# STM32.net
KiCad netlist of a schematic drawn in Altium Designer
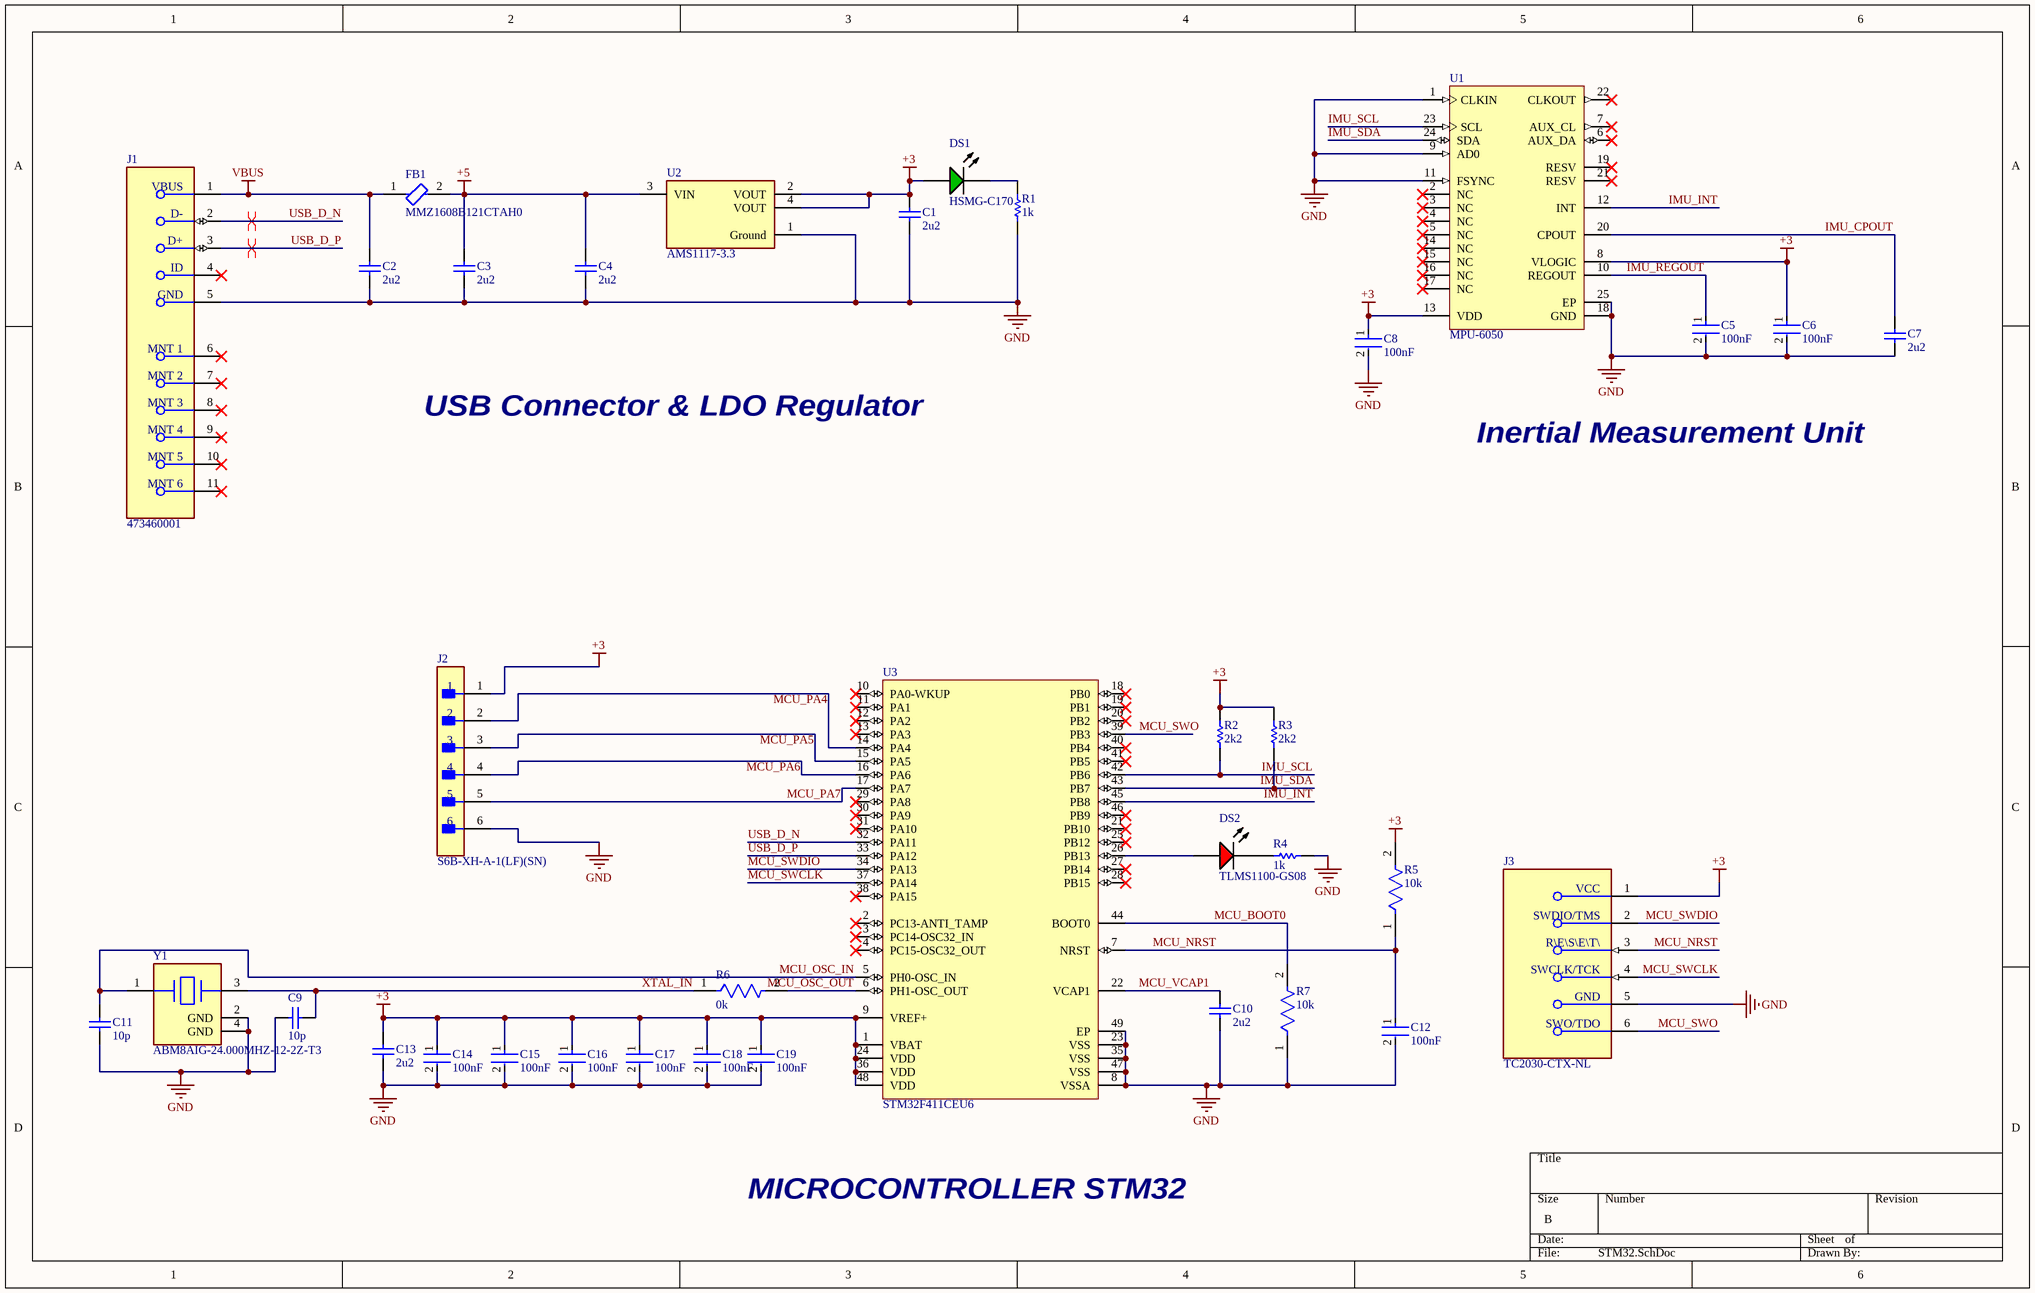
[diagram p0: STM32.SchDoc]

(export (version "E")
  (design (tool "Eeschema 10.0.6"))
  (components
    (comp (ref "C1")
      (value "2u2")
      (footprint "CAPC2013X135X50ML10T20")
      (fields (field (name "MANUFACTURER") "Murata") (field (name "PART NUMBER") "GRM21BR71C225KA12L"))
      (libsource (lib "Altium Content Vault") (part "CAP"))
    )
    (comp (ref "C2")
      (value "2u2")
      (footprint "CAPC2013X135X50ML10T20")
      (fields (field (name "MANUFACTURER") "Murata") (field (name "PART NUMBER") "GRM21BR71C225KA12L"))
      (libsource (lib "Altium Content Vault") (part "CAP"))
    )
    (comp (ref "C3")
      (value "2u2")
      (footprint "CAPC2013X135X50ML10T20")
      (fields (field (name "MANUFACTURER") "Murata") (field (name "PART NUMBER") "GRM21BR71C225KA12L"))
      (libsource (lib "Altium Content Vault") (part "CAP"))
    )
    (comp (ref "C4")
      (value "2u2")
      (footprint "CAPC2013X135X50ML10T20")
      (fields (field (name "MANUFACTURER") "Murata") (field (name "PART NUMBER") "GRM21BR71C225KA12L"))
      (libsource (lib "Altium Content Vault") (part "CAP"))
    )
    (comp (ref "C5")
      (value "100nF")
      (footprint "FP-C0603C-CF-MFG")
      (description "Capacitor; Ceramic; Cap; .100uF; Tol 10%; SMT; Vol-Rtg 16V; X7R; Tape and Reel")
      (fields
        (field (name "MANUFACTURER PART NUMBER") "C0603C104K4RACTU")
        (field (name "OCTOPART") "https://octopart.com/c0603c104k4ractu-kemet-93067")
      )
      (libsource (lib "Altium Content Vault") (part "b4654b650e69147ec39a6b967a45e02"))
    )
    (comp (ref "C6")
      (value "100nF")
      (footprint "FP-C0603C-CF-MFG")
      (description "Capacitor; Ceramic; Cap; .100uF; Tol 10%; SMT; Vol-Rtg 16V; X7R; Tape and Reel")
      (fields
        (field (name "MANUFACTURER PART NUMBER") "C0603C104K4RACTU")
        (field (name "OCTOPART") "https://octopart.com/c0603c104k4ractu-kemet-93067")
      )
      (libsource (lib "Altium Content Vault") (part "b4654b650e69147ec39a6b967a45e02"))
    )
    (comp (ref "C7")
      (value "2u2")
      (footprint "CAPC2013X135X50ML10T20")
      (fields (field (name "MANUFACTURER") "Murata") (field (name "PART NUMBER") "GRM21BR71C225KA12L"))
      (libsource (lib "Altium Content Vault") (part "CAP"))
    )
    (comp (ref "C8")
      (value "100nF")
      (footprint "FP-C0603C-CF-MFG")
      (description "Capacitor; Ceramic; Cap; .100uF; Tol 10%; SMT; Vol-Rtg 16V; X7R; Tape and Reel")
      (fields
        (field (name "MANUFACTURER PART NUMBER") "C0603C104K4RACTU")
        (field (name "OCTOPART") "https://octopart.com/c0603c104k4ractu-kemet-93067")
      )
      (libsource (lib "Altium Content Vault") (part "b4654b650e69147ec39a6b967a45e02"))
    )
    (comp (ref "C9")
      (value "10p")
      (footprint "CAPC1006X50X20ML10T10")
      (fields
        (field (name "MANUFACTURER") "AVX Interconnect / Elco")
        (field (name "PART NUMBER") "0402YJ100FBSTR")
      )
      (libsource (lib "Altium Content Vault") (part "CAP"))
    )
    (comp (ref "C10")
      (value "2u2")
      (footprint "CAPC2013X135X50ML10T20")
      (fields (field (name "MANUFACTURER") "Murata") (field (name "PART NUMBER") "GRM21BR71C225KA12L"))
      (libsource (lib "Altium Content Vault") (part "CAP"))
    )
    (comp (ref "C11")
      (value "10p")
      (footprint "CAPC1006X50X20ML10T10")
      (fields
        (field (name "MANUFACTURER") "AVX Interconnect / Elco")
        (field (name "PART NUMBER") "0402YJ100FBSTR")
      )
      (libsource (lib "Altium Content Vault") (part "CAP"))
    )
    (comp (ref "C12")
      (value "100nF")
      (footprint "FP-C0603C-CF-MFG")
      (description "Capacitor; Ceramic; Cap; .100uF; Tol 10%; SMT; Vol-Rtg 16V; X7R; Tape and Reel")
      (fields
        (field (name "MANUFACTURER PART NUMBER") "C0603C104K4RACTU")
        (field (name "OCTOPART") "https://octopart.com/c0603c104k4ractu-kemet-93067")
      )
      (libsource (lib "Altium Content Vault") (part "b4654b650e69147ec39a6b967a45e02"))
    )
    (comp (ref "C13")
      (value "2u2")
      (footprint "CAPC2013X135X50ML10T20")
      (fields (field (name "MANUFACTURER") "Murata") (field (name "PART NUMBER") "GRM21BR71C225KA12L"))
      (libsource (lib "Altium Content Vault") (part "CAP"))
    )
    (comp (ref "C14")
      (value "100nF")
      (footprint "FP-C0603C-CF-MFG")
      (description "Capacitor; Ceramic; Cap; .100uF; Tol 10%; SMT; Vol-Rtg 16V; X7R; Tape and Reel")
      (fields
        (field (name "MANUFACTURER PART NUMBER") "C0603C104K4RACTU")
        (field (name "OCTOPART") "https://octopart.com/c0603c104k4ractu-kemet-93067")
      )
      (libsource (lib "Altium Content Vault") (part "b4654b650e69147ec39a6b967a45e02"))
    )
    (comp (ref "C15")
      (value "100nF")
      (footprint "FP-C0603C-CF-MFG")
      (description "Capacitor; Ceramic; Cap; .100uF; Tol 10%; SMT; Vol-Rtg 16V; X7R; Tape and Reel")
      (fields
        (field (name "MANUFACTURER PART NUMBER") "C0603C104K4RACTU")
        (field (name "OCTOPART") "https://octopart.com/c0603c104k4ractu-kemet-93067")
      )
      (libsource (lib "Altium Content Vault") (part "b4654b650e69147ec39a6b967a45e02"))
    )
    (comp (ref "C16")
      (value "100nF")
      (footprint "FP-C0603C-CF-MFG")
      (description "Capacitor; Ceramic; Cap; .100uF; Tol 10%; SMT; Vol-Rtg 16V; X7R; Tape and Reel")
      (fields
        (field (name "MANUFACTURER PART NUMBER") "C0603C104K4RACTU")
        (field (name "OCTOPART") "https://octopart.com/c0603c104k4ractu-kemet-93067")
      )
      (libsource (lib "Altium Content Vault") (part "b4654b650e69147ec39a6b967a45e02"))
    )
    (comp (ref "C17")
      (value "100nF")
      (footprint "FP-C0603C-CF-MFG")
      (description "Capacitor; Ceramic; Cap; .100uF; Tol 10%; SMT; Vol-Rtg 16V; X7R; Tape and Reel")
      (fields
        (field (name "MANUFACTURER PART NUMBER") "C0603C104K4RACTU")
        (field (name "OCTOPART") "https://octopart.com/c0603c104k4ractu-kemet-93067")
      )
      (libsource (lib "Altium Content Vault") (part "b4654b650e69147ec39a6b967a45e02"))
    )
    (comp (ref "C18")
      (value "100nF")
      (footprint "FP-C0603C-CF-MFG")
      (description "Capacitor; Ceramic; Cap; .100uF; Tol 10%; SMT; Vol-Rtg 16V; X7R; Tape and Reel")
      (fields
        (field (name "MANUFACTURER PART NUMBER") "C0603C104K4RACTU")
        (field (name "OCTOPART") "https://octopart.com/c0603c104k4ractu-kemet-93067")
      )
      (libsource (lib "Altium Content Vault") (part "b4654b650e69147ec39a6b967a45e02"))
    )
    (comp (ref "C19")
      (value "100nF")
      (footprint "FP-C0603C-CF-MFG")
      (description "Capacitor; Ceramic; Cap; .100uF; Tol 10%; SMT; Vol-Rtg 16V; X7R; Tape and Reel")
      (fields
        (field (name "MANUFACTURER PART NUMBER") "C0603C104K4RACTU")
        (field (name "OCTOPART") "https://octopart.com/c0603c104k4ractu-kemet-93067")
      )
      (libsource (lib "Altium Content Vault") (part "b4654b650e69147ec39a6b967a45e02"))
    )
    (comp (ref "DS1")
      (value "HSMG-C170")
      (footprint "AVAG-HSMX-C170_V")
      (description "Chip LED, Green, 2.2 V, -40 to 85 degC, 2-Pin SMD, Pb-Free, Tape and Reel")
      (fields (field (name "MANUFACTURER") "Avago"))
      (libsource (lib "Altium Content Vault") (part "LED_GREEN_A1K2-2"))
    )
    (comp (ref "DS2")
      (value "TLMS1100-GS08")
      (footprint "VISH-TLMX1100_V")
      (description "LED, RED, 2.1 V, -40 to 100 degC, 2-Pin SMD (0603), RoHS, Tape and Reel")
      (fields (field (name "TOLERANCE") "5%"))
      (libsource (lib "Altium Content Vault") (part "LED-RED-AK-2"))
    )
    (comp (ref "FB1")
      (value "MMZ1608B121CTAH0")
      (footprint "FP-MMZ1608-0_6-MFG")
      (description "FERRITE BEAD 120 OHM 0603 1LN")
      (fields (field (name "TOLERANCE") "25%"))
      (libsource (lib "Altium Content Vault") (part "5f30dd21d616792df468990f7003faa"))
    )
    (comp (ref "J1")
      (value "473460001")
      (footprint "FP-473460001-MFG")
      (description "CONN RCPT USB2.0 MICRO B SMD R/A")
      (fields
        (field (name "OCTOPART") "https://octopart.com/47346-0001-molex-7164928")
        (field (name "MANUFACTURER") "Molex")
      )
      (libsource (lib "Altium Content Vault") (part "53ae1f1d9b557310b43ca686e5bb76a"))
    )
    (comp (ref "J2")
      (value "S6B-XH-A-1(LF)(SN)")
      (footprint "FP-S6B-XH-A-1_LF_SN-MFG")
      (description "CONN HEADER R/A P6OS 2.5MM")
      (libsource (lib "Altium Content Vault") (part "f2cb566baf1c37ab5a3b8e90bbeafd6"))
    )
    (comp (ref "J3")
      (value "TC2030-CTX-NL")
      (footprint "FP-TC2030-CTX-NL-MFG")
      (description "6-Pin “No legs” TC2030 Plug-of-Nails™ Cable for use with ARM Cortex processors")
      (libsource (lib "Altium Content Vault") (part "e3fe093a55dc37473f431e03719485e"))
    )
    (comp (ref "R1")
      (value "1k")
      (footprint "RESC2013X60X35ML10T20")
      (description "Chip Resistor, 1 KOhm, +/- 1%, 125 mW, -55 to 155 degC, 0805 (2012 Metric), RoHS, Tape and Reel")
      (fields (field (name "TOLERANCE") "1%") (field (name "MANUFACTURER") "Yageo"))
      (libsource (lib "Altium Content Vault") (part "RES-2"))
    )
    (comp (ref "R2")
      (value "2k2")
      (footprint "RESC1609X50X30ML10T20")
      (fields (field (name "MANUFACTURER") "Vishay Dale") (field (name "PART NUMBER") "CRCW06032R20FKEA"))
      (libsource (lib "Altium Content Vault") (part "RES"))
    )
    (comp (ref "R3")
      (value "2k2")
      (footprint "RESC1609X50X30ML10T20")
      (fields (field (name "MANUFACTURER") "Vishay Dale") (field (name "PART NUMBER") "CRCW06032R20FKEA"))
      (libsource (lib "Altium Content Vault") (part "RES"))
    )
    (comp (ref "R4")
      (value "1k")
      (footprint "RESC2013X60X35ML10T20")
      (description "Chip Resistor, 1 KOhm, +/- 1%, 125 mW, -55 to 155 degC, 0805 (2012 Metric), RoHS, Tape and Reel")
      (fields (field (name "TOLERANCE") "1%") (field (name "MANUFACTURER") "Yageo"))
      (libsource (lib "Altium Content Vault") (part "RES-2"))
    )
    (comp (ref "R5")
      (value "10k")
      (footprint "FP-CRCW0402-e3-IPC_B")
      (description "RES SMD 10K OHM 1% 1/16W 0402")
      (fields (field (name "TOLERANCE") "1%"))
      (libsource (lib "Altium Content Vault") (part "1029c3af85768c4190bb7ad29bc67b5"))
    )
    (comp (ref "R6")
      (value "0k")
      (footprint "FP-CRCW0402-e3-IPC_C")
      (description "RES Thick Film, 0Ω, 0.063W, 0402")
      (fields (field (name "TOLERANCE") "5%"))
      (libsource (lib "Altium Content Vault") (part "1029c3af85768c4190bb7ad29bc67b5"))
    )
    (comp (ref "R7")
      (value "10k")
      (footprint "FP-CRCW0402-e3-IPC_B")
      (description "RES SMD 10K OHM 1% 1/16W 0402")
      (fields (field (name "TOLERANCE") "1%"))
      (libsource (lib "Altium Content Vault") (part "1029c3af85768c4190bb7ad29bc67b5"))
    )
    (comp (ref "U1")
      (value "MPU-6050")
      (footprint "IS-QFN-24_V")
      (fields (field (name "MANUFACTURER") "InvenSense"))
      (libsource (lib "Altium Content Vault") (part "IS-MPU-6050-QFN-24"))
    )
    (comp (ref "U2")
      (value "AMS1117-3.3")
      (footprint "FP-AMS1117-IPC_C")
      (description "LDO Voltage Regulators 1A, 3.3V")
      (fields
        (field (name "OCTOPART") "https://octopart.com/ams1117-3.3-advanced+monolithic+systems-25899300")
        (field (name "MANUFACTURER") "Advanced Monolithic Systems")
      )
      (libsource (lib "Altium Content Vault") (part "8bdbb5f8e77002000e30dd2845d0354"))
    )
    (comp (ref "U3")
      (value "STM32F411CEU6")
      (footprint "STM-UFQFPN48_L")
      (libsource (lib "Altium Content Vault") (part "MC-ARM-STM32F411-UFQFPN48"))
    )
    (comp (ref "Y1")
      (value "ABM8AIG-24.000MHZ-12-2Z-T3")
      (footprint "FP-ABM8AIG-MFG")
      (description "Crystal 24MHz ±20ppm (Tol) ±50ppm (Stability) 12pF FUND 50Ω Automotive 4-Pin Ultra Mini-CSMD T/R")
      (libsource (lib "Altium Content Vault") (part "5645ab55de99a04feaa93ac4102b7fe"))
    )
  )
  (nets
    (net (code "1") (name "+3") (class "Default")
      (node (ref "C1") (pin "2") (pinfunction "2_2") (pintype "passive"))
      (node (ref "C13") (pin "2") (pinfunction "2_2") (pintype "passive"))
      (node (ref "C14") (pin "1") (pinfunction "1_1") (pintype "passive"))
      (node (ref "C15") (pin "1") (pinfunction "1_1") (pintype "passive"))
      (node (ref "C16") (pin "1") (pinfunction "1_1") (pintype "passive"))
      (node (ref "C17") (pin "1") (pinfunction "1_1") (pintype "passive"))
      (node (ref "C18") (pin "1") (pinfunction "1_1") (pintype "passive"))
      (node (ref "C19") (pin "1") (pinfunction "1_1") (pintype "passive"))
      (node (ref "C6") (pin "1") (pinfunction "1_1") (pintype "passive"))
      (node (ref "C8") (pin "1") (pinfunction "1_1") (pintype "passive"))
      (node (ref "DS1") (pin "1") (pinfunction "A_1") (pintype "passive"))
      (node (ref "J2") (pin "1") (pinfunction "1_1") (pintype "passive"))
      (node (ref "J3") (pin "1") (pinfunction "VCC_1") (pintype "power_in"))
      (node (ref "R2") (pin "2") (pinfunction "2_2") (pintype "passive"))
      (node (ref "R3") (pin "2") (pinfunction "2_2") (pintype "passive"))
      (node (ref "R5") (pin "2") (pinfunction "2_2") (pintype "passive"))
      (node (ref "U1") (pin "13") (pinfunction "VDD_13") (pintype "power_in"))
      (node (ref "U1") (pin "8") (pinfunction "VLOGIC_8") (pintype "power_in"))
      (node (ref "U2") (pin "2") (pinfunction "VOUT_2") (pintype "passive"))
      (node (ref "U2") (pin "4") (pinfunction "VOUT_4") (pintype "passive"))
      (node (ref "U3") (pin "1") (pinfunction "VBAT_1") (pintype "power_in"))
      (node (ref "U3") (pin "24") (pinfunction "VDD_24") (pintype "power_in"))
      (node (ref "U3") (pin "36") (pinfunction "VDD_36") (pintype "power_in"))
      (node (ref "U3") (pin "48") (pinfunction "VDD_48") (pintype "power_in"))
      (node (ref "U3") (pin "9") (pinfunction "VREF+_9") (pintype "power_in"))
    )
    (net (code "2") (name "+5") (class "Default")
      (node (ref "C3") (pin "2") (pinfunction "2_2") (pintype "passive"))
      (node (ref "C4") (pin "2") (pinfunction "2_2") (pintype "passive"))
      (node (ref "FB1") (pin "2") (pinfunction "2_2") (pintype "passive"))
      (node (ref "U2") (pin "3") (pinfunction "VIN_3") (pintype "power_in"))
    )
    (net (code "3") (name "/IMU_CPOUT") (class "Default")
      (node (ref "C7") (pin "2") (pinfunction "2_2") (pintype "passive"))
      (node (ref "U1") (pin "20") (pinfunction "CPOUT_20") (pintype "passive"))
    )
    (net (code "4") (name "/IMU_INT") (class "Default")
      (node (ref "U1") (pin "12") (pinfunction "INT_12") (pintype "open_collector"))
      (node (ref "U3") (pin "45") (pinfunction "PB8_45") (pintype "bidirectional"))
    )
    (net (code "5") (name "/IMU_REGOUT") (class "Default")
      (node (ref "C5") (pin "1") (pinfunction "1_1") (pintype "passive"))
      (node (ref "U1") (pin "10") (pinfunction "REGOUT_10") (pintype "passive"))
    )
    (net (code "6") (name "/IMU_SCL") (class "Default")
      (node (ref "R2") (pin "1") (pinfunction "1_1") (pintype "passive"))
      (node (ref "U1") (pin "23") (pinfunction "SCL_23") (pintype "input"))
      (node (ref "U3") (pin "42") (pinfunction "PB6_42") (pintype "bidirectional"))
    )
    (net (code "7") (name "/IMU_SDA") (class "Default")
      (node (ref "R3") (pin "1") (pinfunction "1_1") (pintype "passive"))
      (node (ref "U1") (pin "24") (pinfunction "SDA_24") (pintype "bidirectional"))
      (node (ref "U3") (pin "43") (pinfunction "PB7_43") (pintype "bidirectional"))
    )
    (net (code "8") (name "/MCU_BOOT0") (class "Default")
      (node (ref "R7") (pin "2") (pinfunction "2_2") (pintype "passive"))
      (node (ref "U3") (pin "44") (pinfunction "BOOT0_44") (pintype "passive"))
    )
    (net (code "9") (name "/MCU_NRST") (class "Default")
      (node (ref "C12") (pin "1") (pinfunction "1_1") (pintype "passive"))
      (node (ref "J3") (pin "3") (pinfunction "~{RESET}_3") (pintype "input"))
      (node (ref "R5") (pin "1") (pinfunction "1_1") (pintype "passive"))
      (node (ref "U3") (pin "7") (pinfunction "NRST_7") (pintype "bidirectional"))
    )
    (net (code "10") (name "/MCU_OSC_IN") (class "Default")
      (node (ref "C11") (pin "2") (pinfunction "2_2") (pintype "passive"))
      (node (ref "U3") (pin "5") (pinfunction "PH0-OSC_IN_5") (pintype "bidirectional"))
      (node (ref "Y1") (pin "1") (pinfunction "1_1") (pintype "passive"))
    )
    (net (code "11") (name "/MCU_OSC_OUT") (class "Default")
      (node (ref "R6") (pin "2") (pinfunction "2_2") (pintype "passive"))
      (node (ref "U3") (pin "6") (pinfunction "PH1-OSC_OUT_6") (pintype "bidirectional"))
    )
    (net (code "12") (name "/MCU_PA4") (class "Default")
      (node (ref "J2") (pin "2") (pinfunction "2_2") (pintype "passive"))
      (node (ref "U3") (pin "14") (pinfunction "PA4_14") (pintype "bidirectional"))
    )
    (net (code "13") (name "/MCU_PA5") (class "Default")
      (node (ref "J2") (pin "3") (pinfunction "3_3") (pintype "passive"))
      (node (ref "U3") (pin "15") (pinfunction "PA5_15") (pintype "bidirectional"))
    )
    (net (code "14") (name "/MCU_PA6") (class "Default")
      (node (ref "J2") (pin "4") (pinfunction "4_4") (pintype "passive"))
      (node (ref "U3") (pin "16") (pinfunction "PA6_16") (pintype "bidirectional"))
    )
    (net (code "15") (name "/MCU_PA7") (class "Default")
      (node (ref "J2") (pin "5") (pinfunction "5_5") (pintype "passive"))
      (node (ref "U3") (pin "17") (pinfunction "PA7_17") (pintype "bidirectional"))
    )
    (net (code "16") (name "/MCU_SWCLK") (class "Default")
      (node (ref "J3") (pin "4") (pinfunction "SWCLK/TCK_4") (pintype "input"))
      (node (ref "U3") (pin "37") (pinfunction "PA14_37") (pintype "bidirectional"))
    )
    (net (code "17") (name "/MCU_SWDIO") (class "Default")
      (node (ref "J3") (pin "2") (pinfunction "SWDIO/TMS_2") (pintype "passive"))
      (node (ref "U3") (pin "34") (pinfunction "PA13_34") (pintype "bidirectional"))
    )
    (net (code "18") (name "/MCU_SWO") (class "Default")
      (node (ref "J3") (pin "6") (pinfunction "SWO/TDO_6") (pintype "passive"))
      (node (ref "U3") (pin "39") (pinfunction "PB3_39") (pintype "bidirectional"))
    )
    (net (code "19") (name "/MCU_VCAP1") (class "Default")
      (node (ref "C10") (pin "2") (pinfunction "2_2") (pintype "passive"))
      (node (ref "U3") (pin "22") (pinfunction "VCAP1_22") (pintype "passive"))
    )
    (net (code "20") (name "/USB_D_N") (class "Default")
      (node (ref "J1") (pin "2") (pinfunction "D-_2") (pintype "bidirectional"))
      (node (ref "U3") (pin "32") (pinfunction "PA11_32") (pintype "bidirectional"))
    )
    (net (code "21") (name "/USB_D_P") (class "Default")
      (node (ref "J1") (pin "3") (pinfunction "D+_3") (pintype "bidirectional"))
      (node (ref "U3") (pin "33") (pinfunction "PA12_33") (pintype "bidirectional"))
    )
    (net (code "22") (name "/XTAL_IN") (class "Default")
      (node (ref "C9") (pin "2") (pinfunction "2_2") (pintype "passive"))
      (node (ref "R6") (pin "1") (pinfunction "1_1") (pintype "passive"))
      (node (ref "Y1") (pin "3") (pinfunction "3_3") (pintype "passive"))
    )
    (net (code "23") (name "GND") (class "Default")
      (node (ref "C1") (pin "1") (pinfunction "1_1") (pintype "passive"))
      (node (ref "C10") (pin "1") (pinfunction "1_1") (pintype "passive"))
      (node (ref "C11") (pin "1") (pinfunction "1_1") (pintype "passive"))
      (node (ref "C12") (pin "2") (pinfunction "2_2") (pintype "passive"))
      (node (ref "C13") (pin "1") (pinfunction "1_1") (pintype "passive"))
      (node (ref "C14") (pin "2") (pinfunction "2_2") (pintype "passive"))
      (node (ref "C15") (pin "2") (pinfunction "2_2") (pintype "passive"))
      (node (ref "C16") (pin "2") (pinfunction "2_2") (pintype "passive"))
      (node (ref "C17") (pin "2") (pinfunction "2_2") (pintype "passive"))
      (node (ref "C18") (pin "2") (pinfunction "2_2") (pintype "passive"))
      (node (ref "C19") (pin "2") (pinfunction "2_2") (pintype "passive"))
      (node (ref "C2") (pin "1") (pinfunction "1_1") (pintype "passive"))
      (node (ref "C3") (pin "1") (pinfunction "1_1") (pintype "passive"))
      (node (ref "C4") (pin "1") (pinfunction "1_1") (pintype "passive"))
      (node (ref "C5") (pin "2") (pinfunction "2_2") (pintype "passive"))
      (node (ref "C6") (pin "2") (pinfunction "2_2") (pintype "passive"))
      (node (ref "C7") (pin "1") (pinfunction "1_1") (pintype "passive"))
      (node (ref "C8") (pin "2") (pinfunction "2_2") (pintype "passive"))
      (node (ref "C9") (pin "1") (pinfunction "1_1") (pintype "passive"))
      (node (ref "J1") (pin "5") (pinfunction "GND_5") (pintype "power_in"))
      (node (ref "J2") (pin "6") (pinfunction "6_6") (pintype "passive"))
      (node (ref "J3") (pin "5") (pinfunction "GND_5") (pintype "power_in"))
      (node (ref "R1") (pin "1") (pinfunction "1_1") (pintype "passive"))
      (node (ref "R4") (pin "2") (pinfunction "2_2") (pintype "passive"))
      (node (ref "R7") (pin "1") (pinfunction "1_1") (pintype "passive"))
      (node (ref "U1") (pin "1") (pinfunction "CLKIN_1") (pintype "input"))
      (node (ref "U1") (pin "11") (pinfunction "FSYNC_11") (pintype "input"))
      (node (ref "U1") (pin "18") (pinfunction "GND_18") (pintype "power_in"))
      (node (ref "U1") (pin "25") (pinfunction "EP_25") (pintype "power_in"))
      (node (ref "U1") (pin "9") (pinfunction "AD0_9") (pintype "input"))
      (node (ref "U2") (pin "1") (pinfunction "Ground_1") (pintype "power_in"))
      (node (ref "U3") (pin "23") (pinfunction "VSS_23") (pintype "power_in"))
      (node (ref "U3") (pin "35") (pinfunction "VSS_35") (pintype "power_in"))
      (node (ref "U3") (pin "47") (pinfunction "VSS_47") (pintype "power_in"))
      (node (ref "U3") (pin "49") (pinfunction "EP_49") (pintype "power_in"))
      (node (ref "U3") (pin "8") (pinfunction "VSSA_8") (pintype "power_in"))
      (node (ref "Y1") (pin "2") (pinfunction "GND_2") (pintype "power_in"))
      (node (ref "Y1") (pin "4") (pinfunction "GND_4") (pintype "power_in"))
    )
    (net (code "24") (name "Net-(DS1-K)") (class "Default")
      (node (ref "DS1") (pin "2") (pinfunction "K_2") (pintype "passive"))
      (node (ref "R1") (pin "2") (pinfunction "2_2") (pintype "passive"))
    )
    (net (code "25") (name "Net-(DS2-A)") (class "Default")
      (node (ref "DS2") (pin "1") (pinfunction "A_1") (pintype "passive"))
      (node (ref "U3") (pin "26") (pinfunction "PB13_26") (pintype "bidirectional"))
    )
    (net (code "26") (name "Net-(DS2-K)") (class "Default")
      (node (ref "DS2") (pin "2") (pinfunction "K_2") (pintype "passive"))
      (node (ref "R4") (pin "1") (pinfunction "1_1") (pintype "passive"))
    )
    (net (code "27") (name "VBUS") (class "Default")
      (node (ref "C2") (pin "2") (pinfunction "2_2") (pintype "passive"))
      (node (ref "FB1") (pin "1") (pinfunction "1_1") (pintype "passive"))
      (node (ref "J1") (pin "1") (pinfunction "VBUS_1") (pintype "power_in"))
    )
    (net (code "28") (name "unconnected-(J1-ID-Pad4)") (class "Default")
      (node (ref "J1") (pin "4") (pinfunction "ID_4") (pintype "passive+no_connect"))
    )
    (net (code "29") (name "unconnected-(J1-MNT_1-Pad6)") (class "Default")
      (node (ref "J1") (pin "6") (pinfunction "MNT_1_6") (pintype "passive+no_connect"))
    )
    (net (code "30") (name "unconnected-(J1-MNT_2-Pad7)") (class "Default")
      (node (ref "J1") (pin "7") (pinfunction "MNT_2_7") (pintype "passive+no_connect"))
    )
    (net (code "31") (name "unconnected-(J1-MNT_3-Pad8)") (class "Default")
      (node (ref "J1") (pin "8") (pinfunction "MNT_3_8") (pintype "passive+no_connect"))
    )
    (net (code "32") (name "unconnected-(J1-MNT_4-Pad9)") (class "Default")
      (node (ref "J1") (pin "9") (pinfunction "MNT_4_9") (pintype "passive+no_connect"))
    )
    (net (code "33") (name "unconnected-(J1-MNT_5-Pad10)") (class "Default")
      (node (ref "J1") (pin "10") (pinfunction "MNT_5_10") (pintype "passive+no_connect"))
    )
    (net (code "34") (name "unconnected-(J1-MNT_6-Pad11)") (class "Default")
      (node (ref "J1") (pin "11") (pinfunction "MNT_6_11") (pintype "passive+no_connect"))
    )
    (net (code "35") (name "unconnected-(U1-AUX_CL-Pad7)") (class "Default")
      (node (ref "U1") (pin "7") (pinfunction "AUX_CL_7") (pintype "output+no_connect"))
    )
    (net (code "36") (name "unconnected-(U1-AUX_DA-Pad6)") (class "Default")
      (node (ref "U1") (pin "6") (pinfunction "AUX_DA_6") (pintype "bidirectional+no_connect"))
    )
    (net (code "37") (name "unconnected-(U1-CLKOUT-Pad22)") (class "Default")
      (node (ref "U1") (pin "22") (pinfunction "CLKOUT_22") (pintype "output+no_connect"))
    )
    (net (code "38") (name "unconnected-(U1-NC-Pad2)") (class "Default")
      (node (ref "U1") (pin "2") (pinfunction "NC_2") (pintype "passive+no_connect"))
    )
    (net (code "39") (name "unconnected-(U1-NC-Pad3)") (class "Default")
      (node (ref "U1") (pin "3") (pinfunction "NC_3") (pintype "passive+no_connect"))
    )
    (net (code "40") (name "unconnected-(U1-NC-Pad4)") (class "Default")
      (node (ref "U1") (pin "4") (pinfunction "NC_4") (pintype "passive+no_connect"))
    )
    (net (code "41") (name "unconnected-(U1-NC-Pad5)") (class "Default")
      (node (ref "U1") (pin "5") (pinfunction "NC_5") (pintype "passive+no_connect"))
    )
    (net (code "42") (name "unconnected-(U1-NC-Pad14)") (class "Default")
      (node (ref "U1") (pin "14") (pinfunction "NC_14") (pintype "passive+no_connect"))
    )
    (net (code "43") (name "unconnected-(U1-NC-Pad15)") (class "Default")
      (node (ref "U1") (pin "15") (pinfunction "NC_15") (pintype "passive+no_connect"))
    )
    (net (code "44") (name "unconnected-(U1-NC-Pad16)") (class "Default")
      (node (ref "U1") (pin "16") (pinfunction "NC_16") (pintype "passive+no_connect"))
    )
    (net (code "45") (name "unconnected-(U1-NC-Pad17)") (class "Default")
      (node (ref "U1") (pin "17") (pinfunction "NC_17") (pintype "passive+no_connect"))
    )
    (net (code "46") (name "unconnected-(U1-RESV-Pad19)") (class "Default")
      (node (ref "U1") (pin "19") (pinfunction "RESV_19") (pintype "passive+no_connect"))
    )
    (net (code "47") (name "unconnected-(U1-RESV-Pad21)") (class "Default")
      (node (ref "U1") (pin "21") (pinfunction "RESV_21") (pintype "passive+no_connect"))
    )
    (net (code "48") (name "unconnected-(U3-PA0-WKUP-Pad10)") (class "Default")
      (node (ref "U3") (pin "10") (pinfunction "PA0-WKUP_10") (pintype "bidirectional+no_connect"))
    )
    (net (code "49") (name "unconnected-(U3-PA1-Pad11)") (class "Default")
      (node (ref "U3") (pin "11") (pinfunction "PA1_11") (pintype "bidirectional+no_connect"))
    )
    (net (code "50") (name "unconnected-(U3-PA2-Pad12)") (class "Default")
      (node (ref "U3") (pin "12") (pinfunction "PA2_12") (pintype "bidirectional+no_connect"))
    )
    (net (code "51") (name "unconnected-(U3-PA3-Pad13)") (class "Default")
      (node (ref "U3") (pin "13") (pinfunction "PA3_13") (pintype "bidirectional+no_connect"))
    )
    (net (code "52") (name "unconnected-(U3-PA8-Pad29)") (class "Default")
      (node (ref "U3") (pin "29") (pinfunction "PA8_29") (pintype "bidirectional+no_connect"))
    )
    (net (code "53") (name "unconnected-(U3-PA9-Pad30)") (class "Default")
      (node (ref "U3") (pin "30") (pinfunction "PA9_30") (pintype "bidirectional+no_connect"))
    )
    (net (code "54") (name "unconnected-(U3-PA10-Pad31)") (class "Default")
      (node (ref "U3") (pin "31") (pinfunction "PA10_31") (pintype "bidirectional+no_connect"))
    )
    (net (code "55") (name "unconnected-(U3-PA15-Pad38)") (class "Default")
      (node (ref "U3") (pin "38") (pinfunction "PA15_38") (pintype "bidirectional+no_connect"))
    )
    (net (code "56") (name "unconnected-(U3-PB0-Pad18)") (class "Default")
      (node (ref "U3") (pin "18") (pinfunction "PB0_18") (pintype "bidirectional+no_connect"))
    )
    (net (code "57") (name "unconnected-(U3-PB1-Pad19)") (class "Default")
      (node (ref "U3") (pin "19") (pinfunction "PB1_19") (pintype "bidirectional+no_connect"))
    )
    (net (code "58") (name "unconnected-(U3-PB2-Pad20)") (class "Default")
      (node (ref "U3") (pin "20") (pinfunction "PB2_20") (pintype "bidirectional+no_connect"))
    )
    (net (code "59") (name "unconnected-(U3-PB4-Pad40)") (class "Default")
      (node (ref "U3") (pin "40") (pinfunction "PB4_40") (pintype "bidirectional+no_connect"))
    )
    (net (code "60") (name "unconnected-(U3-PB5-Pad41)") (class "Default")
      (node (ref "U3") (pin "41") (pinfunction "PB5_41") (pintype "bidirectional+no_connect"))
    )
    (net (code "61") (name "unconnected-(U3-PB9-Pad46)") (class "Default")
      (node (ref "U3") (pin "46") (pinfunction "PB9_46") (pintype "bidirectional+no_connect"))
    )
    (net (code "62") (name "unconnected-(U3-PB10-Pad21)") (class "Default")
      (node (ref "U3") (pin "21") (pinfunction "PB10_21") (pintype "bidirectional+no_connect"))
    )
    (net (code "63") (name "unconnected-(U3-PB12-Pad25)") (class "Default")
      (node (ref "U3") (pin "25") (pinfunction "PB12_25") (pintype "bidirectional+no_connect"))
    )
    (net (code "64") (name "unconnected-(U3-PB14-Pad27)") (class "Default")
      (node (ref "U3") (pin "27") (pinfunction "PB14_27") (pintype "bidirectional+no_connect"))
    )
    (net (code "65") (name "unconnected-(U3-PB15-Pad28)") (class "Default")
      (node (ref "U3") (pin "28") (pinfunction "PB15_28") (pintype "bidirectional+no_connect"))
    )
    (net (code "66") (name "unconnected-(U3-PC13-ANTI_TAMP-Pad2)") (class "Default")
      (node (ref "U3") (pin "2") (pinfunction "PC13-ANTI_TAMP_2") (pintype "bidirectional+no_connect"))
    )
    (net (code "67") (name "unconnected-(U3-PC14-OSC32_IN-Pad3)") (class "Default")
      (node (ref "U3") (pin "3") (pinfunction "PC14-OSC32_IN_3") (pintype "bidirectional+no_connect"))
    )
    (net (code "68") (name "unconnected-(U3-PC15-OSC32_OUT-Pad4)") (class "Default")
      (node (ref "U3") (pin "4") (pinfunction "PC15-OSC32_OUT_4") (pintype "bidirectional+no_connect"))
    )
  )
)
